# OSP_Carrier_V7_Release_PMIC_Audio.net
KiCad netlist of a schematic drawn in Altium Designer
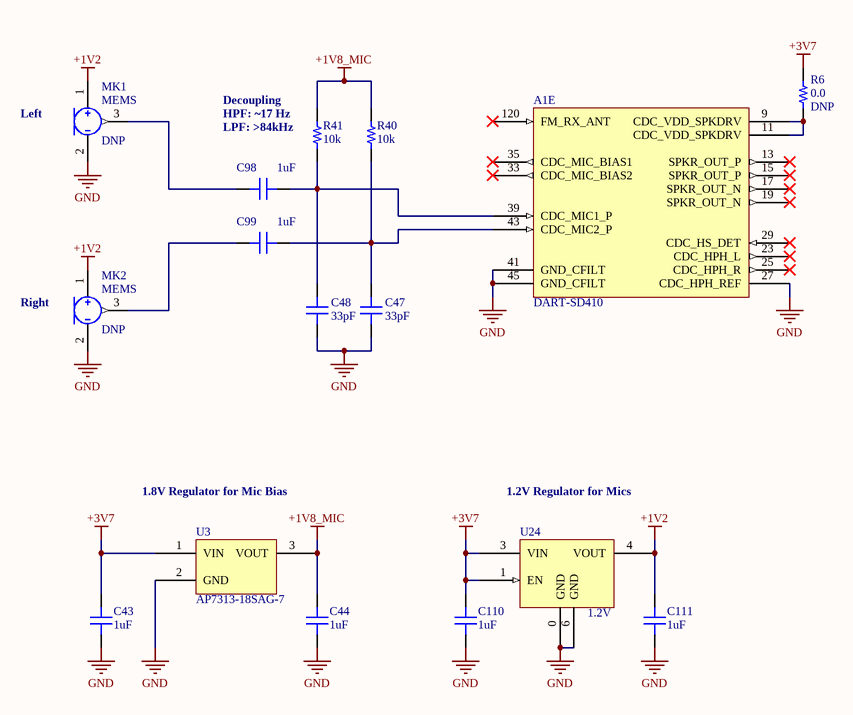
[diagram p0: OSP_Carrier_V7_Release_PMIC_Audio.SchDoc]

(export (version "E")
  (design (tool "Eeschema 10.0.6"))
  (components
    (comp (ref "A1")
      (value "DART-SD410")
      (footprint "DART-SD410")
      (description "Variscite DART-SD410 System on Module")
      (libsource (lib "DART-SD410") (part "DART-SD410"))
    )
    (comp (ref "C43")
      (value "1uF")
      (footprint "CAP 0402/1005")
      (description "CAP CER 1UF 10V X5R 0402")
      (fields
        (field (name "PART NUMBER") "GRM155R61A105KE15D")
        (field (name "MANUFACTURER") "Murata Electronics North America")
      )
      (libsource (lib "Celestial Library Database") (part "Capacitor"))
    )
    (comp (ref "C44")
      (value "1uF")
      (footprint "CAP 0402/1005")
      (description "CAP CER 1UF 10V X5R 0402")
      (fields
        (field (name "PART NUMBER") "GRM155R61A105KE15D")
        (field (name "MANUFACTURER") "Murata Electronics North America")
      )
      (libsource (lib "Celestial Library Database") (part "Capacitor"))
    )
    (comp (ref "C47")
      (value "33pF")
      (footprint "CAP 0402/1005")
      (description "CAP CER 33PF 50V C0G 0402")
      (fields
        (field (name "PART NUMBER") "C1005C0G1H330J050BA")
        (field (name "MANUFACTURER") "TDK Corporation")
      )
      (libsource (lib "Celestial Library Database") (part "Capacitor"))
    )
    (comp (ref "C48")
      (value "33pF")
      (footprint "CAP 0402/1005")
      (description "CAP CER 33PF 50V C0G 0402")
      (fields
        (field (name "PART NUMBER") "C1005C0G1H330J050BA")
        (field (name "MANUFACTURER") "TDK Corporation")
      )
      (libsource (lib "Celestial Library Database") (part "Capacitor"))
    )
    (comp (ref "C98")
      (value "1uF")
      (footprint "CAP 0603/1608")
      (description "CAP CER 1UF 25V X7R 0603")
      (fields
        (field (name "PART NUMBER") "C1608X7R1E105K080AB")
        (field (name "MANUFACTURER") "TDK Corporation")
      )
      (libsource (lib "Celestial Library Database") (part "Capacitor"))
    )
    (comp (ref "C99")
      (value "1uF")
      (footprint "CAP 0603/1608")
      (description "CAP CER 1UF 25V X7R 0603")
      (fields
        (field (name "PART NUMBER") "C1608X7R1E105K080AB")
        (field (name "MANUFACTURER") "TDK Corporation")
      )
      (libsource (lib "Celestial Library Database") (part "Capacitor"))
    )
    (comp (ref "C110")
      (value "1uF")
      (footprint "CAP 0402/1005")
      (description "CAP CER 1UF 10V X5R 0402")
      (fields
        (field (name "PART NUMBER") "GRM155R61A105KE15D")
        (field (name "MANUFACTURER") "Murata Electronics North America")
      )
      (libsource (lib "Celestial Library Database") (part "Capacitor"))
    )
    (comp (ref "C111")
      (value "1uF")
      (footprint "CAP 0402/1005")
      (description "CAP CER 1UF 10V X5R 0402")
      (fields
        (field (name "PART NUMBER") "GRM155R61A105KE15D")
        (field (name "MANUFACTURER") "Murata Electronics North America")
      )
      (libsource (lib "Celestial Library Database") (part "Capacitor"))
    )
    (comp (ref "MK1")
      (value "MEMS")
      (footprint "MEMS_MIC")
      (description "Generic 3-pin bottom mount MEMS mic")
      (fields (field (name "DNP") "DNP"))
      (libsource (lib "OSP_Symbols") (part "Mems_Mic"))
    )
    (comp (ref "MK2")
      (value "MEMS")
      (footprint "MEMS_MIC")
      (description "Generic 3-pin bottom mount MEMS mic")
      (fields (field (name "DNP") "DNP"))
      (libsource (lib "OSP_Symbols") (part "Mems_Mic"))
    )
    (comp (ref "R6")
      (value "0.0")
      (footprint "RES 0603/1608")
      (description "RES SMD 0.0 OHM JUMPER 1/4W 0603")
      (fields
        (field (name "PART NUMBER") "CRCW06030000Z0EAHP")
        (field (name "MANUFACTURER") "Vishay Dale")
        (field (name "DNP") "DNP")
      )
      (libsource (lib "Celestial Library Database") (part "Resistor"))
    )
    (comp (ref "R40")
      (value "10k")
      (footprint "RES 0402/1005")
      (description "RES SMD 10K OHM 1% 1/10W 0402")
      (fields
        (field (name "PART NUMBER") "ERJ-2RKF1002X")
        (field (name "MANUFACTURER") "Panasonic Electronic Components")
      )
      (libsource (lib "Celestial Library Database") (part "Resistor"))
    )
    (comp (ref "R41")
      (value "10k")
      (footprint "RES 0402/1005")
      (description "RES SMD 10K OHM 1% 1/10W 0402")
      (fields
        (field (name "PART NUMBER") "ERJ-2RKF1002X")
        (field (name "MANUFACTURER") "Panasonic Electronic Components")
      )
      (libsource (lib "Celestial Library Database") (part "Resistor"))
    )
    (comp (ref "U3")
      (value "AP7313-18SAG-7")
      (footprint "DIODES SOT-23-3")
      (description "IC REG LDO 1.8V 0.15A SOT23-3")
      (fields (field (name "MANUFACTURER") "Diodes Incorporated"))
      (libsource (lib "Celestial Library Database") (part "Diodes Inc AP7313"))
    )
    (comp (ref "U24")
      (value "1.2V")
      (footprint "MICROCHIP_MIC5512")
      (description "Microchip MIC5512-1.2YMT 1.2V 300mA linear regulator")
      (libsource (lib "OSP_Symbols") (part "Microchip_MIC5512-1.2YMT"))
    )
  )
  (nets
    (net (code "1") (name "+1V2") (class "Default")
      (node (ref "C111") (pin "1") (pinfunction "1_1") (pintype "passive"))
      (node (ref "MK1") (pin "1") (pinfunction "VDD_1") (pintype "power_in"))
      (node (ref "MK2") (pin "1") (pinfunction "VDD_1") (pintype "power_in"))
      (node (ref "U24") (pin "4") (pinfunction "VOUT_4") (pintype "power_in"))
    )
    (net (code "2") (name "+1V8_MIC") (class "Default")
      (node (ref "C44") (pin "1") (pinfunction "1_1") (pintype "passive"))
      (node (ref "R40") (pin "2") (pinfunction "2_2") (pintype "passive"))
      (node (ref "R41") (pin "2") (pinfunction "2_2") (pintype "passive"))
      (node (ref "U3") (pin "3") (pinfunction "VOUT_3") (pintype "passive"))
    )
    (net (code "3") (name "+3V7") (class "Default")
      (node (ref "C110") (pin "1") (pinfunction "1_1") (pintype "passive"))
      (node (ref "C43") (pin "1") (pinfunction "1_1") (pintype "passive"))
      (node (ref "R6") (pin "2") (pinfunction "2_2") (pintype "passive"))
      (node (ref "U24") (pin "1") (pinfunction "EN_1") (pintype "input"))
      (node (ref "U24") (pin "3") (pinfunction "VIN_3") (pintype "power_in"))
      (node (ref "U3") (pin "1") (pinfunction "VIN_1") (pintype "passive"))
    )
    (net (code "4") (name "GND") (class "Default")
      (node (ref "A1") (pin "27") (pinfunction "CDC_HPH_REF_27") (pintype "power_in"))
      (node (ref "A1") (pin "41") (pinfunction "GND_CFILT_41") (pintype "power_in"))
      (node (ref "A1") (pin "45") (pinfunction "GND_CFILT_45") (pintype "power_in"))
      (node (ref "C110") (pin "2") (pinfunction "2_2") (pintype "passive"))
      (node (ref "C111") (pin "2") (pinfunction "2_2") (pintype "passive"))
      (node (ref "C43") (pin "2") (pinfunction "2_2") (pintype "passive"))
      (node (ref "C44") (pin "2") (pinfunction "2_2") (pintype "passive"))
      (node (ref "C47") (pin "1") (pinfunction "1_1") (pintype "passive"))
      (node (ref "C48") (pin "1") (pinfunction "1_1") (pintype "passive"))
      (node (ref "MK1") (pin "2") (pinfunction "GND_2") (pintype "power_in"))
      (node (ref "MK2") (pin "2") (pinfunction "GND_2") (pintype "power_in"))
      (node (ref "U24") (pin "0") (pinfunction "GND_0") (pintype "power_in"))
      (node (ref "U24") (pin "6") (pinfunction "GND_6") (pintype "power_in"))
      (node (ref "U3") (pin "2") (pinfunction "GND_2") (pintype "passive"))
    )
    (net (code "5") (name "Net-(A1E-CDC_MIC1_P)") (class "Default")
      (node (ref "A1") (pin "39") (pinfunction "CDC_MIC1_P_39") (pintype "input"))
      (node (ref "C48") (pin "2") (pinfunction "2_2") (pintype "passive"))
      (node (ref "C98") (pin "1") (pinfunction "1_1") (pintype "passive"))
      (node (ref "R41") (pin "1") (pinfunction "1_1") (pintype "passive"))
    )
    (net (code "6") (name "Net-(A1E-CDC_MIC2_P)") (class "Default")
      (node (ref "A1") (pin "43") (pinfunction "CDC_MIC2_P_43") (pintype "input"))
      (node (ref "C47") (pin "2") (pinfunction "2_2") (pintype "passive"))
      (node (ref "C99") (pin "1") (pinfunction "1_1") (pintype "passive"))
      (node (ref "R40") (pin "1") (pinfunction "1_1") (pintype "passive"))
    )
    (net (code "7") (name "Net-(A1E-CDC_VDD_SPKDRV-Pad11)") (class "Default")
      (node (ref "A1") (pin "11") (pinfunction "CDC_VDD_SPKDRV_11") (pintype "power_in"))
      (node (ref "A1") (pin "9") (pinfunction "CDC_VDD_SPKDRV_9") (pintype "power_in"))
      (node (ref "R6") (pin "1") (pinfunction "1_1") (pintype "passive"))
    )
    (net (code "8") (name "Net-(C98-Pad2)") (class "Default")
      (node (ref "C98") (pin "2") (pinfunction "2_2") (pintype "passive"))
      (node (ref "MK1") (pin "3") (pintype "output"))
    )
    (net (code "9") (name "Net-(C99-Pad2)") (class "Default")
      (node (ref "C99") (pin "2") (pinfunction "2_2") (pintype "passive"))
      (node (ref "MK2") (pin "3") (pintype "output"))
    )
    (net (code "10") (name "unconnected-(A1E-CDC_HPH_L-Pad23)") (class "Default")
      (node (ref "A1") (pin "23") (pinfunction "CDC_HPH_L_23") (pintype "output+no_connect"))
    )
    (net (code "11") (name "unconnected-(A1E-CDC_HPH_R-Pad25)") (class "Default")
      (node (ref "A1") (pin "25") (pinfunction "CDC_HPH_R_25") (pintype "output+no_connect"))
    )
    (net (code "12") (name "unconnected-(A1E-CDC_HS_DET-Pad29)") (class "Default")
      (node (ref "A1") (pin "29") (pinfunction "CDC_HS_DET_29") (pintype "input+no_connect"))
    )
    (net (code "13") (name "unconnected-(A1E-CDC_MIC_BIAS1-Pad35)") (class "Default")
      (node (ref "A1") (pin "35") (pinfunction "CDC_MIC_BIAS1_35") (pintype "output+no_connect"))
    )
    (net (code "14") (name "unconnected-(A1E-CDC_MIC_BIAS2-Pad33)") (class "Default")
      (node (ref "A1") (pin "33") (pinfunction "CDC_MIC_BIAS2_33") (pintype "output+no_connect"))
    )
    (net (code "15") (name "unconnected-(A1E-FM_RX_ANT-Pad120)") (class "Default")
      (node (ref "A1") (pin "120") (pinfunction "FM_RX_ANT_120") (pintype "input+no_connect"))
    )
    (net (code "16") (name "unconnected-(A1E-SPKR_OUT_N-Pad17)") (class "Default")
      (node (ref "A1") (pin "17") (pinfunction "SPKR_OUT_N_17") (pintype "output+no_connect"))
    )
    (net (code "17") (name "unconnected-(A1E-SPKR_OUT_N-Pad19)") (class "Default")
      (node (ref "A1") (pin "19") (pinfunction "SPKR_OUT_N_19") (pintype "output+no_connect"))
    )
    (net (code "18") (name "unconnected-(A1E-SPKR_OUT_P-Pad13)") (class "Default")
      (node (ref "A1") (pin "13") (pinfunction "SPKR_OUT_P_13") (pintype "output+no_connect"))
    )
    (net (code "19") (name "unconnected-(A1E-SPKR_OUT_P-Pad15)") (class "Default")
      (node (ref "A1") (pin "15") (pinfunction "SPKR_OUT_P_15") (pintype "output+no_connect"))
    )
  )
)
